# 1.net
KiCad netlist of a schematic drawn in Altium Designer
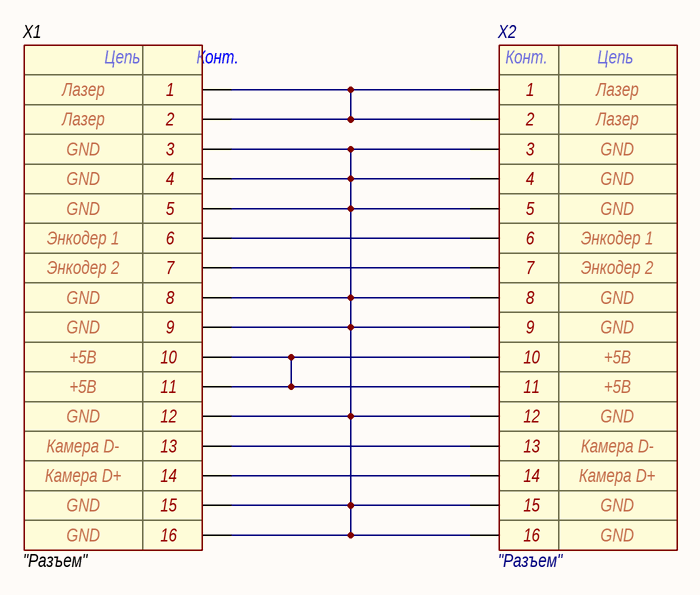
[diagram p0: Лист 1.SchDoc]

(export (version "E")
  (design (tool "Eeschema 10.0.6"))
  (components
    (comp (ref "X1")
      (value "~")
      (footprint "CustomCase:CON: IDC-16MS")
      (fields
        (field (name "MANUFACTURER") "Connfly")
        (field (name "VALUEMANUFACTURERPARTNUMBER") "Connector, 16pin, 2.54mm, 250VAC, 3A")
        (field (name "PARTNUMBER") "IDC-16")
        (field (name "COMMENTTEXT") "\"Разъем\"")
      )
      (libsource (lib "Connector") (part "IDC-16"))
    )
    (comp (ref "X2")
      (value "\"Разъем\"")
      (footprint "CustomCase:CON: 52207-1633, FFC / FPC")
      (libsource (lib "Connector") (part "52207-1633, FFC / FPC"))
    )
  )
  (nets
    (net (code "1") (name "Net-(X1-Pad1)") (class "Default")
      (node (ref "X1") (pin "1") (pinfunction "1_1") (pintype "passive"))
      (node (ref "X1") (pin "2") (pinfunction "2_2") (pintype "passive"))
      (node (ref "X2") (pin "1") (pinfunction "1_1") (pintype "passive"))
      (node (ref "X2") (pin "2") (pinfunction "2_2") (pintype "passive"))
    )
    (net (code "2") (name "Net-(X1-Pad6)") (class "Default")
      (node (ref "X1") (pin "6") (pinfunction "6_6") (pintype "power_in"))
      (node (ref "X2") (pin "6") (pinfunction "6_6") (pintype "power_in"))
    )
    (net (code "3") (name "Net-(X1-Pad7)") (class "Default")
      (node (ref "X1") (pin "7") (pinfunction "7_7") (pintype "power_in"))
      (node (ref "X2") (pin "7") (pinfunction "7_7") (pintype "power_in"))
    )
    (net (code "4") (name "Net-(X1-Pad10)") (class "Default")
      (node (ref "X1") (pin "10") (pinfunction "10_10") (pintype "power_in"))
      (node (ref "X1") (pin "11") (pinfunction "11_11") (pintype "power_in"))
      (node (ref "X2") (pin "10") (pinfunction "10_10") (pintype "power_in"))
      (node (ref "X2") (pin "11") (pinfunction "11_11") (pintype "power_in"))
    )
    (net (code "5") (name "Net-(X1-Pad12)") (class "Default")
      (node (ref "X1") (pin "12") (pinfunction "12_12") (pintype "power_in"))
      (node (ref "X1") (pin "15") (pinfunction "15_15") (pintype "power_in"))
      (node (ref "X1") (pin "16") (pinfunction "16_16") (pintype "power_in"))
      (node (ref "X1") (pin "3") (pinfunction "3_3") (pintype "power_in"))
      (node (ref "X1") (pin "4") (pinfunction "4_4") (pintype "power_in"))
      (node (ref "X1") (pin "5") (pinfunction "5_5") (pintype "power_in"))
      (node (ref "X1") (pin "8") (pinfunction "8_8") (pintype "power_in"))
      (node (ref "X1") (pin "9") (pinfunction "9_9") (pintype "power_in"))
      (node (ref "X2") (pin "12") (pinfunction "12_12") (pintype "power_in"))
      (node (ref "X2") (pin "15") (pinfunction "15_15") (pintype "power_in"))
      (node (ref "X2") (pin "16") (pinfunction "16_16") (pintype "power_in"))
      (node (ref "X2") (pin "3") (pinfunction "3_3") (pintype "power_in"))
      (node (ref "X2") (pin "4") (pinfunction "4_4") (pintype "power_in"))
      (node (ref "X2") (pin "5") (pinfunction "5_5") (pintype "power_in"))
      (node (ref "X2") (pin "8") (pinfunction "8_8") (pintype "power_in"))
      (node (ref "X2") (pin "9") (pinfunction "9_9") (pintype "power_in"))
    )
    (net (code "6") (name "Net-(X1-Pad13)") (class "Default")
      (node (ref "X1") (pin "13") (pinfunction "13_13") (pintype "power_in"))
      (node (ref "X2") (pin "13") (pinfunction "13_13") (pintype "power_in"))
    )
    (net (code "7") (name "Net-(X1-Pad14)") (class "Default")
      (node (ref "X1") (pin "14") (pinfunction "14_14") (pintype "power_in"))
      (node (ref "X2") (pin "14") (pinfunction "14_14") (pintype "power_in"))
    )
  )
)
